# arm_v3.net
KiCad netlist of a schematic drawn in Altium Designer
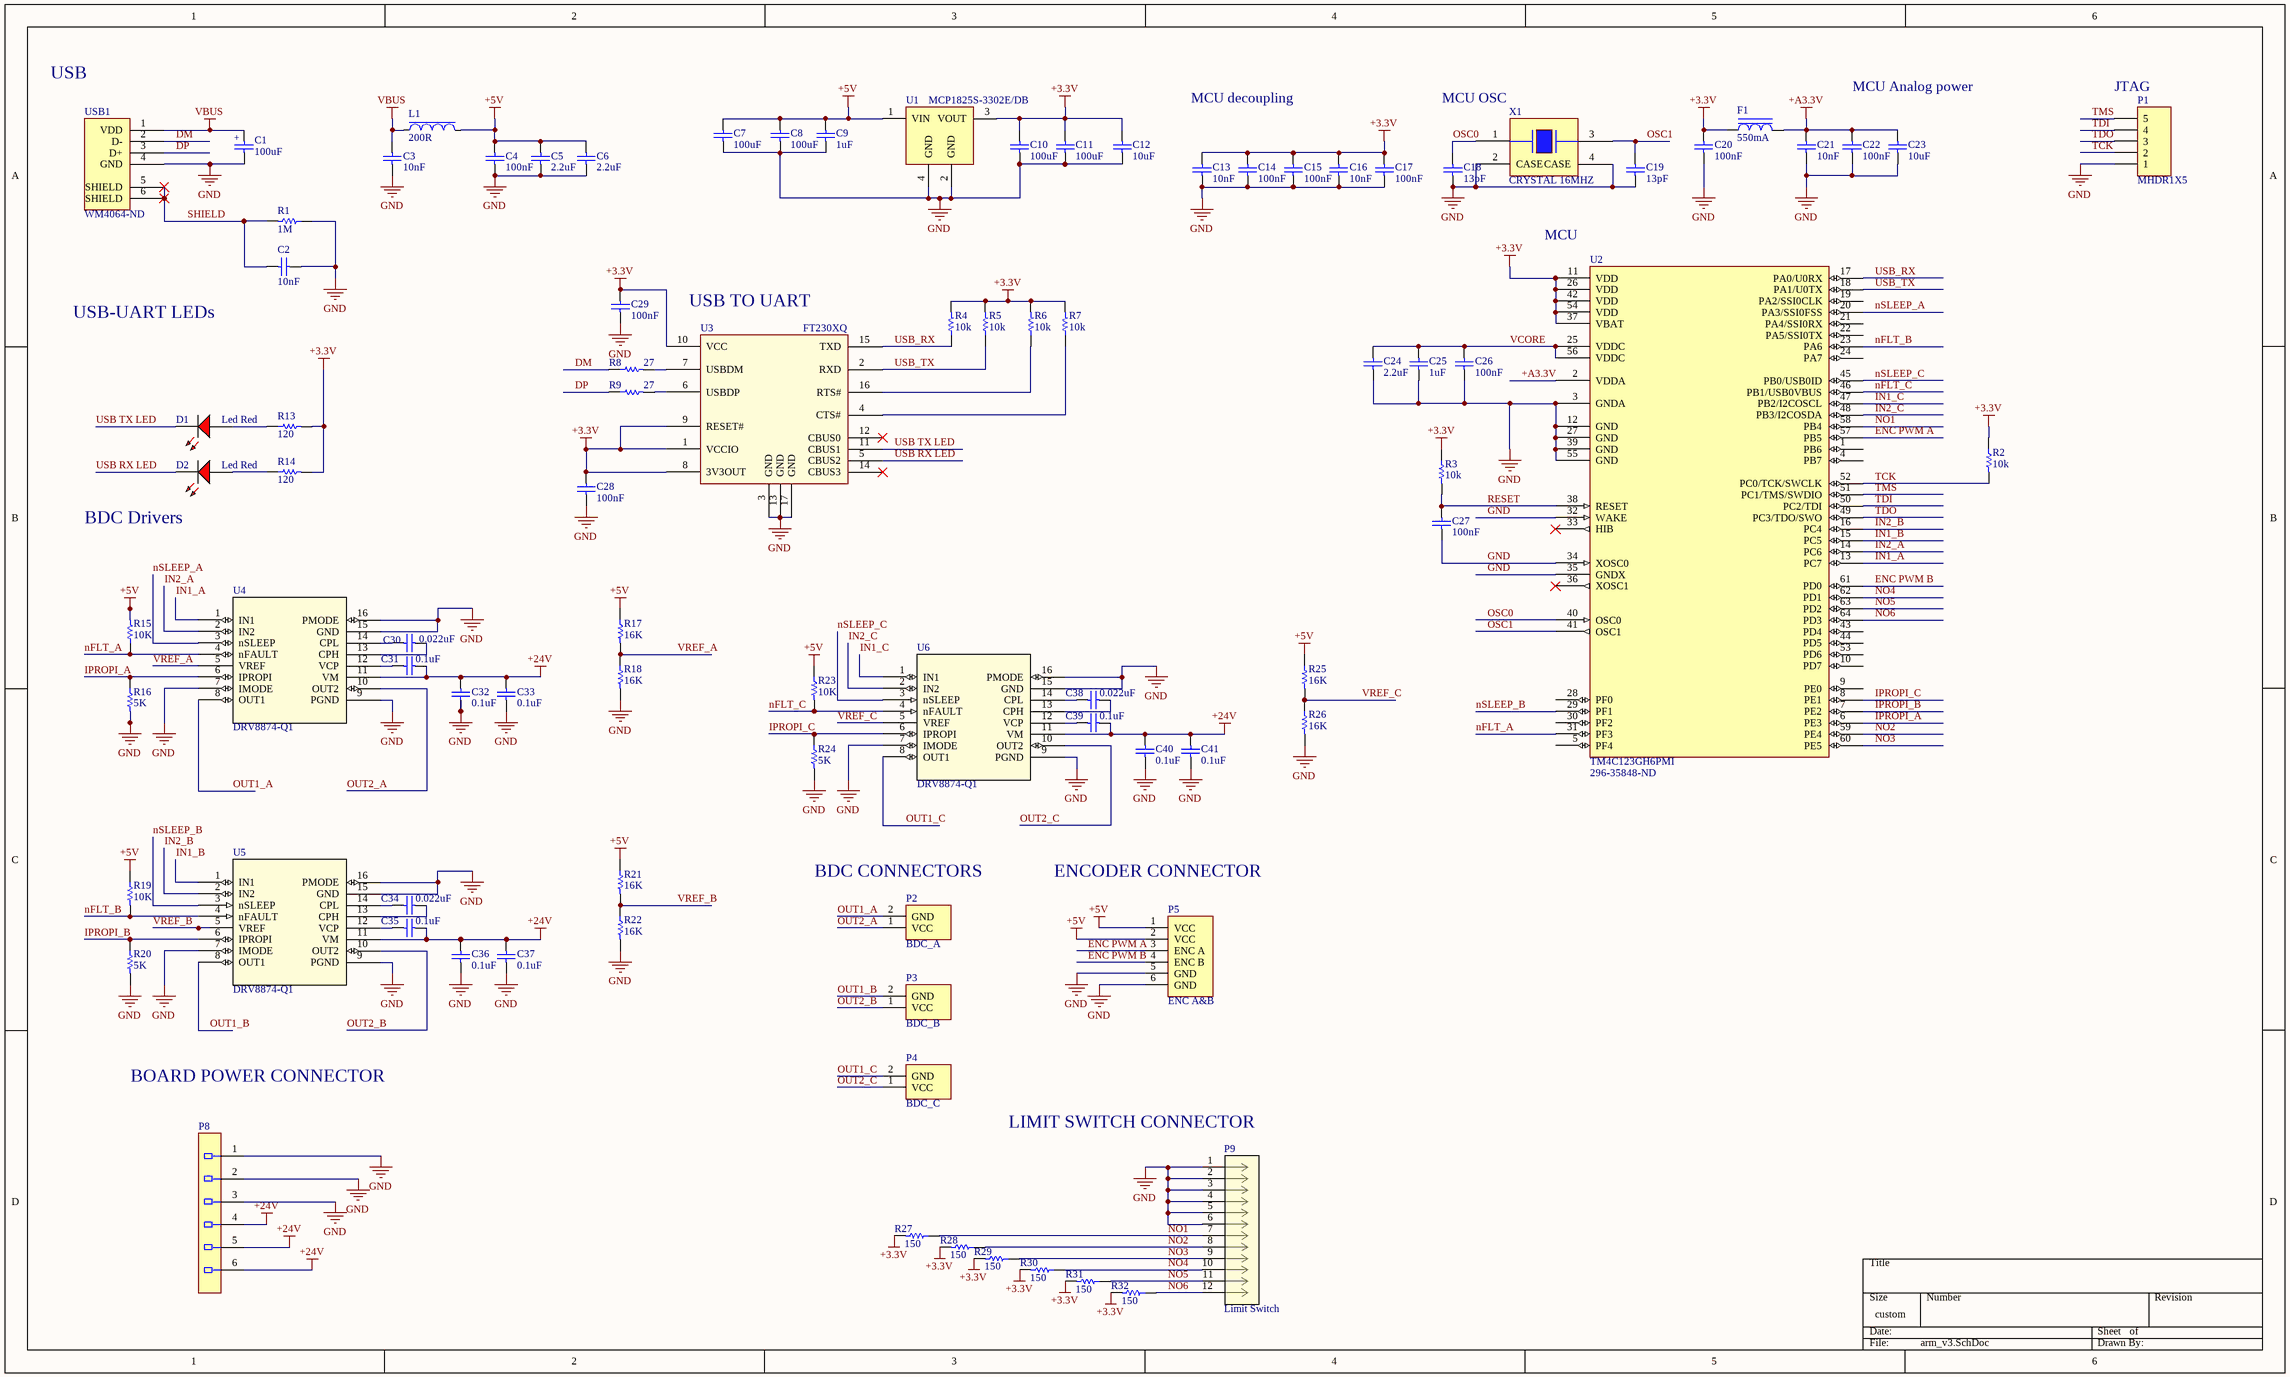
[diagram p0: arm_v3.SchDoc]

(export (version "E")
  (design (tool "Eeschema 10.0.6"))
  (components
    (comp (ref "C1")
      (value "100uF")
      (footprint "CapAlu6.3mmx12.5mm")
      (description "Capacitor 35v 100uF 6.3mm")
      (fields
        (field (name "MANUFACTURER") "Nichicon")
        (field (name "MANUFACTURER PART NUMBER") "UHV1V101MED")
      )
      (libsource (lib "Capacitors") (part "100uF_35v_6.3x12.5"))
    )
    (comp (ref "C2")
      (value "10nF")
      (footprint "CAP_1206")
      (description "CAP CER 10000PF 500V X7R 1206")
      (fields
        (field (name "MANUFACTURER") "Samsung Electro-Mechanics America, Inc")
        (field (name "MANUFACTURER PART NUMBER") "CL31B103KGFNNNE")
      )
      (libsource (lib "Capacitors") (part "10nF_500V_1206"))
    )
    (comp (ref "C3")
      (value "10nF")
      (footprint "CAP_0402_M")
      (description "CAP CER 10000PF 50V 10% X7R 0402")
      (fields
        (field (name "MANUFACTURER") "Kemet")
        (field (name "MANUFACTURER PART NUMBER") "C0402C103K5RACTU")
      )
      (libsource (lib "Capacitors") (part "10nF_50V_0402"))
    )
    (comp (ref "C4")
      (value "100nF")
      (footprint "CAP_0402_M")
      (description "CAP CER 100NF 50V 20% X5R 0402")
      (fields
        (field (name "MANUFACTURER") "TDK Corporation")
        (field (name "MANUFACTURER PART NUMBER") "C1005X5R1H104M050BB")
      )
      (libsource (lib "Capacitors") (part "100nF_50V_0402"))
    )
    (comp (ref "C5")
      (value "2.2uF")
      (footprint "CAP_0402_M")
      (description "CAP CER 2.2UF 10V 20% X5R 0402")
      (fields
        (field (name "MANUFACTURER") "Taiyo Yuden")
        (field (name "MANUFACTURER PART NUMBER") "LMK105BJ225MV-F")
      )
      (libsource (lib "Capacitors") (part "2.2uF_10V_0402"))
    )
    (comp (ref "C6")
      (value "2.2uF")
      (footprint "CAP_0402_M")
      (description "CAP CER 2.2UF 10V 20% X5R 0402")
      (fields
        (field (name "MANUFACTURER") "Taiyo Yuden")
        (field (name "MANUFACTURER PART NUMBER") "LMK105BJ225MV-F")
      )
      (libsource (lib "Capacitors") (part "2.2uF_10V_0402"))
    )
    (comp (ref "C7")
      (value "100uF")
      (footprint "CAP_1206")
      (description "CAP CER 100UF 6.3V X5R 1206")
      (fields
        (field (name "MANUFACTURER") "Murata Electronics North America")
        (field (name "MANUFACTURER PART NUMBER") "GRM31CR60J107ME39L")
      )
      (libsource (lib "Capacitors") (part "100uF_6.3v_1206_X5R"))
    )
    (comp (ref "C8")
      (value "100uF")
      (footprint "CAP_1206")
      (description "CAP CER 100UF 6.3V X5R 1206")
      (fields
        (field (name "MANUFACTURER") "Murata Electronics North America")
        (field (name "MANUFACTURER PART NUMBER") "GRM31CR60J107ME39L")
      )
      (libsource (lib "Capacitors") (part "100uF_6.3v_1206_X5R"))
    )
    (comp (ref "C9")
      (value "1uF")
      (footprint "CAP_0402_M")
      (description "CAP CER 1UF 25V 10% X5R 0402")
      (fields
        (field (name "MANUFACTURER") "TDK Corporation")
        (field (name "MANUFACTURER PART NUMBER") "C1005X5R1E105K050BC")
      )
      (libsource (lib "Capacitors") (part "1uF_25V_0402"))
    )
    (comp (ref "C10")
      (value "100uF")
      (footprint "CAP_1206")
      (description "CAP CER 100UF 6.3V X5R 1206")
      (fields
        (field (name "MANUFACTURER") "Murata Electronics North America")
        (field (name "MANUFACTURER PART NUMBER") "GRM31CR60J107ME39L")
      )
      (libsource (lib "Capacitors") (part "100uF_6.3v_1206_X5R"))
    )
    (comp (ref "C11")
      (value "100uF")
      (footprint "CAP_1206")
      (description "CAP CER 100UF 6.3V X5R 1206")
      (fields
        (field (name "MANUFACTURER") "Murata Electronics North America")
        (field (name "MANUFACTURER PART NUMBER") "GRM31CR60J107ME39L")
      )
      (libsource (lib "Capacitors") (part "100uF_6.3v_1206_X5R"))
    )
    (comp (ref "C12")
      (value "10uF")
      (footprint "CAP_0603")
      (description "CAP CER 10UF 10V 20% X5R 0603")
      (fields
        (field (name "MANUFACTURER") "Taiyo Yuden")
        (field (name "MANUFACTURER PART NUMBER") "LMK107BBJ106MAHT")
      )
      (libsource (lib "Capacitors") (part "10uF_10V_0603"))
    )
    (comp (ref "C13")
      (value "10nF")
      (footprint "CAP_0402_M")
      (description "CAP CER 10000PF 50V 10% X7R 0402")
      (fields
        (field (name "MANUFACTURER") "Kemet")
        (field (name "MANUFACTURER PART NUMBER") "C0402C103K5RACTU")
      )
      (libsource (lib "Capacitors") (part "10nF_50V_0402"))
    )
    (comp (ref "C14")
      (value "100nF")
      (footprint "CAP_0402_M")
      (description "CAP CER 100NF 50V 20% X5R 0402")
      (fields
        (field (name "MANUFACTURER") "TDK Corporation")
        (field (name "MANUFACTURER PART NUMBER") "C1005X5R1H104M050BB")
      )
      (libsource (lib "Capacitors") (part "100nF_50V_0402"))
    )
    (comp (ref "C15")
      (value "100nF")
      (footprint "CAP_0402_M")
      (description "CAP CER 100NF 50V 20% X5R 0402")
      (fields
        (field (name "MANUFACTURER") "TDK Corporation")
        (field (name "MANUFACTURER PART NUMBER") "C1005X5R1H104M050BB")
      )
      (libsource (lib "Capacitors") (part "100nF_50V_0402"))
    )
    (comp (ref "C16")
      (value "10nF")
      (footprint "CAP_0402_M")
      (description "CAP CER 10000PF 50V 10% X7R 0402")
      (fields
        (field (name "MANUFACTURER") "Kemet")
        (field (name "MANUFACTURER PART NUMBER") "C0402C103K5RACTU")
      )
      (libsource (lib "Capacitors") (part "10nF_50V_0402"))
    )
    (comp (ref "C17")
      (value "100nF")
      (footprint "CAP_0402_M")
      (description "CAP CER 100NF 50V 20% X5R 0402")
      (fields
        (field (name "MANUFACTURER") "TDK Corporation")
        (field (name "MANUFACTURER PART NUMBER") "C1005X5R1H104M050BB")
      )
      (libsource (lib "Capacitors") (part "100nF_50V_0402"))
    )
    (comp (ref "C18")
      (value "13pF")
      (footprint "CAP_0402_M")
      (description "CAP CER 13PF 50V 5% NP0 0402")
      (fields
        (field (name "MANUFACTURER") "Samsung Electro-Mechanics America, Inc")
        (field (name "MANUFACTURER PART NUMBER") "CL05C130JB5NNNC")
      )
      (libsource (lib "Capacitors") (part "13pF_50V_0402"))
    )
    (comp (ref "C19")
      (value "13pF")
      (footprint "CAP_0402_M")
      (description "CAP CER 13PF 50V 5% NP0 0402")
      (fields
        (field (name "MANUFACTURER") "Samsung Electro-Mechanics America, Inc")
        (field (name "MANUFACTURER PART NUMBER") "CL05C130JB5NNNC")
      )
      (libsource (lib "Capacitors") (part "13pF_50V_0402"))
    )
    (comp (ref "C20")
      (value "100nF")
      (footprint "CAP_0402_M")
      (description "CAP CER 100NF 50V 20% X5R 0402")
      (fields
        (field (name "MANUFACTURER") "TDK Corporation")
        (field (name "MANUFACTURER PART NUMBER") "C1005X5R1H104M050BB")
      )
      (libsource (lib "Capacitors") (part "100nF_50V_0402"))
    )
    (comp (ref "C21")
      (value "10nF")
      (footprint "CAP_0402_M")
      (description "CAP CER 10000PF 50V 10% X7R 0402")
      (fields
        (field (name "MANUFACTURER") "Kemet")
        (field (name "MANUFACTURER PART NUMBER") "C0402C103K5RACTU")
      )
      (libsource (lib "Capacitors") (part "10nF_50V_0402"))
    )
    (comp (ref "C22")
      (value "100nF")
      (footprint "CAP_0402_M")
      (description "CAP CER 100NF 50V 20% X5R 0402")
      (fields
        (field (name "MANUFACTURER") "TDK Corporation")
        (field (name "MANUFACTURER PART NUMBER") "C1005X5R1H104M050BB")
      )
      (libsource (lib "Capacitors") (part "100nF_50V_0402"))
    )
    (comp (ref "C23")
      (value "10uF")
      (footprint "CAP_0603")
      (description "CAP CER 10UF 10V 20% X5R 0603")
      (fields
        (field (name "MANUFACTURER") "Taiyo Yuden")
        (field (name "MANUFACTURER PART NUMBER") "LMK107BBJ106MAHT")
      )
      (libsource (lib "Capacitors") (part "10uF_10V_0603"))
    )
    (comp (ref "C24")
      (value "2.2uF")
      (footprint "CAP_0603")
      (description "CAP CER 2.2UF 35V 10% X5R 0603")
      (fields
        (field (name "MANUFACTURER") "Murata Electronics North America")
        (field (name "MANUFACTURER PART NUMBER") "GRM188R6YA225KA12D")
      )
      (libsource (lib "Capacitors") (part "2.2uF_35V_0603"))
    )
    (comp (ref "C25")
      (value "1uF")
      (footprint "CAP_0402_M")
      (description "CAP CER 1UF 25V 10% X5R 0402")
      (fields
        (field (name "MANUFACTURER") "TDK Corporation")
        (field (name "MANUFACTURER PART NUMBER") "C1005X5R1E105K050BC")
      )
      (libsource (lib "Capacitors") (part "1uF_25V_0402"))
    )
    (comp (ref "C26")
      (value "100nF")
      (footprint "CAP_0402_M")
      (description "CAP CER 100NF 50V 20% X5R 0402")
      (fields
        (field (name "MANUFACTURER") "TDK Corporation")
        (field (name "MANUFACTURER PART NUMBER") "C1005X5R1H104M050BB")
      )
      (libsource (lib "Capacitors") (part "100nF_50V_0402"))
    )
    (comp (ref "C27")
      (value "100nF")
      (footprint "CAP_0402_M")
      (description "CAP CER 100NF 50V 20% X5R 0402")
      (fields
        (field (name "MANUFACTURER") "TDK Corporation")
        (field (name "MANUFACTURER PART NUMBER") "C1005X5R1H104M050BB")
      )
      (libsource (lib "Capacitors") (part "100nF_50V_0402"))
    )
    (comp (ref "C28")
      (value "100nF")
      (footprint "CAP_0402_M")
      (description "CAP CER 100NF 50V 20% X5R 0402")
      (fields
        (field (name "MANUFACTURER") "TDK Corporation")
        (field (name "MANUFACTURER PART NUMBER") "C1005X5R1H104M050BB")
      )
      (libsource (lib "Capacitors") (part "100nF_50V_0402"))
    )
    (comp (ref "C29")
      (value "100nF")
      (footprint "CAP_0402_M")
      (description "CAP CER 100NF 50V 20% X5R 0402")
      (fields
        (field (name "MANUFACTURER") "TDK Corporation")
        (field (name "MANUFACTURER PART NUMBER") "C1005X5R1H104M050BB")
      )
      (libsource (lib "Capacitors") (part "100nF_50V_0402"))
    )
    (comp (ref "C30")
      (value "0.022uF")
      (footprint "CAP_0402_M")
      (description "CAP CER 100NF 50V 20% X5R 0402")
      (fields
        (field (name "MANUFACTURER") "TDK Corporation")
        (field (name "MANUFACTURER PART NUMBER") "C1005X5R1H104M050BB")
      )
      (libsource (lib "Capacitors") (part "100nF_50V_0402"))
    )
    (comp (ref "C31")
      (value "0.1uF")
      (footprint "CAP_0402_M")
      (description "CAP CER 100NF 50V 20% X5R 0402")
      (fields
        (field (name "MANUFACTURER") "TDK Corporation")
        (field (name "MANUFACTURER PART NUMBER") "C1005X5R1H104M050BB")
      )
      (libsource (lib "Capacitors") (part "100nF_50V_0402"))
    )
    (comp (ref "C32")
      (value "0.1uF")
      (footprint "CAP_0402_M")
      (description "CAP CER 100NF 50V 20% X5R 0402")
      (fields
        (field (name "MANUFACTURER") "TDK Corporation")
        (field (name "MANUFACTURER PART NUMBER") "C1005X5R1H104M050BB")
      )
      (libsource (lib "Capacitors") (part "100nF_50V_0402"))
    )
    (comp (ref "C33")
      (value "0.1uF")
      (footprint "CAP_0402_M")
      (description "CAP CER 100NF 50V 20% X5R 0402")
      (fields
        (field (name "MANUFACTURER") "TDK Corporation")
        (field (name "MANUFACTURER PART NUMBER") "C1005X5R1H104M050BB")
      )
      (libsource (lib "Capacitors") (part "100nF_50V_0402"))
    )
    (comp (ref "C34")
      (value "0.022uF")
      (footprint "CAP_0402_M")
      (description "CAP CER 100NF 50V 20% X5R 0402")
      (fields
        (field (name "MANUFACTURER") "TDK Corporation")
        (field (name "MANUFACTURER PART NUMBER") "C1005X5R1H104M050BB")
      )
      (libsource (lib "Capacitors") (part "100nF_50V_0402"))
    )
    (comp (ref "C35")
      (value "0.1uF")
      (footprint "CAP_0402_M")
      (description "CAP CER 100NF 50V 20% X5R 0402")
      (fields
        (field (name "MANUFACTURER") "TDK Corporation")
        (field (name "MANUFACTURER PART NUMBER") "C1005X5R1H104M050BB")
      )
      (libsource (lib "Capacitors") (part "100nF_50V_0402"))
    )
    (comp (ref "C36")
      (value "0.1uF")
      (footprint "CAP_0402_M")
      (description "CAP CER 100NF 50V 20% X5R 0402")
      (fields
        (field (name "MANUFACTURER") "TDK Corporation")
        (field (name "MANUFACTURER PART NUMBER") "C1005X5R1H104M050BB")
      )
      (libsource (lib "Capacitors") (part "100nF_50V_0402"))
    )
    (comp (ref "C37")
      (value "0.1uF")
      (footprint "CAP_0402_M")
      (description "CAP CER 100NF 50V 20% X5R 0402")
      (fields
        (field (name "MANUFACTURER") "TDK Corporation")
        (field (name "MANUFACTURER PART NUMBER") "C1005X5R1H104M050BB")
      )
      (libsource (lib "Capacitors") (part "100nF_50V_0402"))
    )
    (comp (ref "C38")
      (value "0.022uF")
      (footprint "CAP_0402_M")
      (description "CAP CER 100NF 50V 20% X5R 0402")
      (fields
        (field (name "MANUFACTURER") "TDK Corporation")
        (field (name "MANUFACTURER PART NUMBER") "C1005X5R1H104M050BB")
      )
      (libsource (lib "Capacitors") (part "100nF_50V_0402"))
    )
    (comp (ref "C39")
      (value "0.1uF")
      (footprint "CAP_0402_M")
      (description "CAP CER 100NF 50V 20% X5R 0402")
      (fields
        (field (name "MANUFACTURER") "TDK Corporation")
        (field (name "MANUFACTURER PART NUMBER") "C1005X5R1H104M050BB")
      )
      (libsource (lib "Capacitors") (part "100nF_50V_0402"))
    )
    (comp (ref "C40")
      (value "0.1uF")
      (footprint "CAP_0402_M")
      (description "CAP CER 100NF 50V 20% X5R 0402")
      (fields
        (field (name "MANUFACTURER") "TDK Corporation")
        (field (name "MANUFACTURER PART NUMBER") "C1005X5R1H104M050BB")
      )
      (libsource (lib "Capacitors") (part "100nF_50V_0402"))
    )
    (comp (ref "C41")
      (value "0.1uF")
      (footprint "CAP_0402_M")
      (description "CAP CER 100NF 50V 20% X5R 0402")
      (fields
        (field (name "MANUFACTURER") "TDK Corporation")
        (field (name "MANUFACTURER PART NUMBER") "C1005X5R1H104M050BB")
      )
      (libsource (lib "Capacitors") (part "100nF_50V_0402"))
    )
    (comp (ref "D1")
      (value "Led Red")
      (footprint "TOPLED 0805")
      (description "LED TOPLED 630NM SUP RED CLR SMD")
      (fields
        (field (name "MANUFACTURER") "OSRAM Opto Semiconductors Inc")
        (field (name "MANUFACTURER PART NUMBER") "LS M67K-H2L1-1-Z")
      )
      (libsource (lib "Diodes") (part "TOPLED 0803"))
    )
    (comp (ref "D2")
      (value "Led Red")
      (footprint "TOPLED 0805")
      (description "LED TOPLED 630NM SUP RED CLR SMD")
      (fields
        (field (name "MANUFACTURER") "OSRAM Opto Semiconductors Inc")
        (field (name "MANUFACTURER PART NUMBER") "LS M67K-H2L1-1-Z")
      )
      (libsource (lib "Diodes") (part "TOPLED 0803"))
    )
    (comp (ref "F1")
      (value "550mA")
      (footprint "RES_0402_M")
      (description "FERRITE CHIP 40 OHM 550MA 0402")
      (fields
        (field (name "MANUFACTURER") "TDK Corporation")
        (field (name "MANUFACTURER PART NUMBER") "MMZ1005Y400CT000")
      )
      (libsource (lib "Resistors") (part "40O_550mA_0402"))
    )
    (comp (ref "L1")
      (value "200R")
      (footprint "IND_0603")
      (description "FILTER CHIP 220 OHM 2A 0603")
      (fields
        (field (name "MANUFACTURER") "Murata Electronics North America")
        (field (name "MANUFACTURER PART NUMBER") "BLM18EG221SN1D")
      )
      (libsource (lib "Inductors") (part "Ferrite_200 ohms_2A"))
    )
    (comp (ref "P1")
      (value "MHDR1X5")
      (footprint "MHDR1X5")
      (description "Header, 5-Pin")
      (fields (field (name "PUBLISHER") "Altium Limited"))
      (libsource (lib "Miscellaneous Connectors") (part "MHDR1X5"))
    )
    (comp (ref "P2")
      (value "BDC_A")
      (footprint "SamacSys:436500227")
      (description "Connector")
      (fields (field (name "MANUFACTURER_PART_NUMBER") "43650-0227"))
      (libsource (lib "*") (part "43650-0227"))
    )
    (comp (ref "P3")
      (value "BDC_B")
      (footprint "SamacSys:436500227")
      (description "Connector")
      (fields (field (name "MANUFACTURER_PART_NUMBER") "43650-0227"))
      (libsource (lib "*") (part "43650-0227"))
    )
    (comp (ref "P4")
      (value "BDC_C")
      (footprint "SamacSys:436500227")
      (description "Connector")
      (fields (field (name "MANUFACTURER_PART_NUMBER") "43650-0227"))
      (libsource (lib "*") (part "43650-0227"))
    )
    (comp (ref "P5")
      (value "ENC A&B")
      (footprint "SamacSys:1053091106")
      (description "Connector")
      (fields (field (name "MANUFACTURER_PART_NUMBER") "105309-1106"))
      (libsource (lib "*") (part "105309-1106"))
    )
    (comp (ref "P8") (value "76825-0006") (libsource (lib "Molex 76825-0006") (part "76825-0006")))
    (comp (ref "P9")
      (value "Limit Switch")
      (footprint "CON_1053141112")
      (description "No Description Available")
      (fields
        (field (name "MANUFACTURER_PART_NUMBER") "1053141112")
        (field (name "COPYRIGHT") "Copyright (C) 2018 Accelerated Designs. All rights reserved")
      )
      (libsource (lib "Molex 1053141112") (part "1053141112"))
    )
    (comp (ref "R1")
      (value "1M")
      (footprint "RES_1206")
      (description "RES SMD 1M OHM 5% 1/4W 1206")
      (fields
        (field (name "MANUFACTURER") "Panasonic Electronic Components")
        (field (name "MANUFACTURER PART NUMBER") "ERJ-8GEYJ105V")
      )
      (libsource (lib "Resistors") (part "1M_5%_1206"))
    )
    (comp (ref "R2")
      (value "10k")
      (footprint "RES_0402_M")
      (description "RES SMD 10K OHM 1% 1/10W 0402")
      (fields
        (field (name "MANUFACTURER") "Panasonic Electronic Components")
        (field (name "MANUFACTURER PART NUMBER") "ERJ-2RKF1002X")
      )
      (libsource (lib "Resistors") (part "10k_1%_0402"))
    )
    (comp (ref "R3")
      (value "10k")
      (footprint "RES_0402_M")
      (description "RES SMD 10K OHM 1% 1/10W 0402")
      (fields
        (field (name "MANUFACTURER") "Panasonic Electronic Components")
        (field (name "MANUFACTURER PART NUMBER") "ERJ-2RKF1002X")
      )
      (libsource (lib "Resistors") (part "10k_1%_0402"))
    )
    (comp (ref "R4")
      (value "10k")
      (footprint "RES_0402_M")
      (description "RES SMD 10K OHM 1% 1/10W 0402")
      (fields
        (field (name "MANUFACTURER") "Panasonic Electronic Components")
        (field (name "MANUFACTURER PART NUMBER") "ERJ-2RKF1002X")
      )
      (libsource (lib "Resistors") (part "10k_1%_0402"))
    )
    (comp (ref "R5")
      (value "10k")
      (footprint "RES_0402_M")
      (description "RES SMD 10K OHM 1% 1/10W 0402")
      (fields
        (field (name "MANUFACTURER") "Panasonic Electronic Components")
        (field (name "MANUFACTURER PART NUMBER") "ERJ-2RKF1002X")
      )
      (libsource (lib "Resistors") (part "10k_1%_0402"))
    )
    (comp (ref "R6")
      (value "10k")
      (footprint "RES_0402_M")
      (description "RES SMD 10K OHM 1% 1/10W 0402")
      (fields
        (field (name "MANUFACTURER") "Panasonic Electronic Components")
        (field (name "MANUFACTURER PART NUMBER") "ERJ-2RKF1002X")
      )
      (libsource (lib "Resistors") (part "10k_1%_0402"))
    )
    (comp (ref "R7")
      (value "10k")
      (footprint "RES_0402_M")
      (description "RES SMD 10K OHM 1% 1/10W 0402")
      (fields
        (field (name "MANUFACTURER") "Panasonic Electronic Components")
        (field (name "MANUFACTURER PART NUMBER") "ERJ-2RKF1002X")
      )
      (libsource (lib "Resistors") (part "10k_1%_0402"))
    )
    (comp (ref "R8")
      (value "27")
      (footprint "RES_0402_M")
      (description "RES SMD 27 OHM 1% 1/10W 0402")
      (fields
        (field (name "MANUFACTURER") "Panasonic Electronic Components")
        (field (name "MANUFACTURER PART NUMBER") "ERJ-2RKF27R0X")
      )
      (libsource (lib "Resistors") (part "27_1%_0402"))
    )
    (comp (ref "R9")
      (value "27")
      (footprint "RES_0402_M")
      (description "RES SMD 27 OHM 1% 1/10W 0402")
      (fields
        (field (name "MANUFACTURER") "Panasonic Electronic Components")
        (field (name "MANUFACTURER PART NUMBER") "ERJ-2RKF27R0X")
      )
      (libsource (lib "Resistors") (part "27_1%_0402"))
    )
    (comp (ref "R13")
      (value "120")
      (footprint "RES_0402_M")
      (description "RES SMD 120 OHM 1% 1/10W 0402")
      (fields
        (field (name "MANUFACTURER") "Panasonic Electronic Components")
        (field (name "MANUFACTURER PART NUMBER") "ERJ-2RKF1200X")
      )
      (libsource (lib "Resistors") (part "120_1%_0402"))
    )
    (comp (ref "R14")
      (value "120")
      (footprint "RES_0402_M")
      (description "RES SMD 120 OHM 1% 1/10W 0402")
      (fields
        (field (name "MANUFACTURER") "Panasonic Electronic Components")
        (field (name "MANUFACTURER PART NUMBER") "ERJ-2RKF1200X")
      )
      (libsource (lib "Resistors") (part "120_1%_0402"))
    )
    (comp (ref "R15")
      (value "10K")
      (footprint "RES_0402_M")
      (description "RES SMD 0 OHM JUMPER 1/16W 0402")
      (fields
        (field (name "MANUFACTURER") "Yageo")
        (field (name "MANUFACTURER PART NUMBER") "RC0402FR-070RL")
      )
      (libsource (lib "Resistors") (part "0_0402"))
    )
    (comp (ref "R16")
      (value "5K")
      (footprint "RES_0402_M")
      (description "RES SMD 0 OHM JUMPER 1/16W 0402")
      (fields
        (field (name "MANUFACTURER") "Yageo")
        (field (name "MANUFACTURER PART NUMBER") "RC0402FR-070RL")
      )
      (libsource (lib "Resistors") (part "0_0402"))
    )
    (comp (ref "R17")
      (value "16K")
      (footprint "RES_0402_M")
      (description "RES SMD 0 OHM JUMPER 1/16W 0402")
      (fields
        (field (name "MANUFACTURER") "Yageo")
        (field (name "MANUFACTURER PART NUMBER") "RC0402FR-070RL")
      )
      (libsource (lib "Resistors") (part "0_0402"))
    )
    (comp (ref "R18")
      (value "16K")
      (footprint "RES_0402_M")
      (description "RES SMD 0 OHM JUMPER 1/16W 0402")
      (fields
        (field (name "MANUFACTURER") "Yageo")
        (field (name "MANUFACTURER PART NUMBER") "RC0402FR-070RL")
      )
      (libsource (lib "Resistors") (part "0_0402"))
    )
    (comp (ref "R19")
      (value "10K")
      (footprint "RES_0402_M")
      (description "RES SMD 0 OHM JUMPER 1/16W 0402")
      (fields
        (field (name "MANUFACTURER") "Yageo")
        (field (name "MANUFACTURER PART NUMBER") "RC0402FR-070RL")
      )
      (libsource (lib "Resistors") (part "0_0402"))
    )
    (comp (ref "R20")
      (value "5K")
      (footprint "RES_0402_M")
      (description "RES SMD 0 OHM JUMPER 1/16W 0402")
      (fields
        (field (name "MANUFACTURER") "Yageo")
        (field (name "MANUFACTURER PART NUMBER") "RC0402FR-070RL")
      )
      (libsource (lib "Resistors") (part "0_0402"))
    )
    (comp (ref "R21")
      (value "16K")
      (footprint "RES_0402_M")
      (description "RES SMD 0 OHM JUMPER 1/16W 0402")
      (fields
        (field (name "MANUFACTURER") "Yageo")
        (field (name "MANUFACTURER PART NUMBER") "RC0402FR-070RL")
      )
      (libsource (lib "Resistors") (part "0_0402"))
    )
    (comp (ref "R22")
      (value "16K")
      (footprint "RES_0402_M")
      (description "RES SMD 0 OHM JUMPER 1/16W 0402")
      (fields
        (field (name "MANUFACTURER") "Yageo")
        (field (name "MANUFACTURER PART NUMBER") "RC0402FR-070RL")
      )
      (libsource (lib "Resistors") (part "0_0402"))
    )
    (comp (ref "R23")
      (value "10K")
      (footprint "RES_0402_M")
      (description "RES SMD 0 OHM JUMPER 1/16W 0402")
      (fields
        (field (name "MANUFACTURER") "Yageo")
        (field (name "MANUFACTURER PART NUMBER") "RC0402FR-070RL")
      )
      (libsource (lib "Resistors") (part "0_0402"))
    )
    (comp (ref "R24")
      (value "5K")
      (footprint "RES_0402_M")
      (description "RES SMD 0 OHM JUMPER 1/16W 0402")
      (fields
        (field (name "MANUFACTURER") "Yageo")
        (field (name "MANUFACTURER PART NUMBER") "RC0402FR-070RL")
      )
      (libsource (lib "Resistors") (part "0_0402"))
    )
    (comp (ref "R25")
      (value "16K")
      (footprint "RES_0402_M")
      (description "RES SMD 0 OHM JUMPER 1/16W 0402")
      (fields
        (field (name "MANUFACTURER") "Yageo")
        (field (name "MANUFACTURER PART NUMBER") "RC0402FR-070RL")
      )
      (libsource (lib "Resistors") (part "0_0402"))
    )
    (comp (ref "R26")
      (value "16K")
      (footprint "RES_0402_M")
      (description "RES SMD 0 OHM JUMPER 1/16W 0402")
      (fields
        (field (name "MANUFACTURER") "Yageo")
        (field (name "MANUFACTURER PART NUMBER") "RC0402FR-070RL")
      )
      (libsource (lib "Resistors") (part "0_0402"))
    )
    (comp (ref "R27")
      (value "150")
      (footprint "RES_0402_M")
      (description "RES SMD 10K OHM 1% 1/10W 0402")
      (fields
        (field (name "MANUFACTURER") "Panasonic Electronic Components")
        (field (name "MANUFACTURER PART NUMBER") "ERJ-2RKF1002X")
      )
      (libsource (lib "Resistors") (part "10k_1%_0402"))
    )
    (comp (ref "R28")
      (value "150")
      (footprint "RES_0402_M")
      (description "RES SMD 10K OHM 1% 1/10W 0402")
      (fields
        (field (name "MANUFACTURER") "Panasonic Electronic Components")
        (field (name "MANUFACTURER PART NUMBER") "ERJ-2RKF1002X")
      )
      (libsource (lib "Resistors") (part "10k_1%_0402"))
    )
    (comp (ref "R29")
      (value "150")
      (footprint "RES_0402_M")
      (description "RES SMD 10K OHM 1% 1/10W 0402")
      (fields
        (field (name "MANUFACTURER") "Panasonic Electronic Components")
        (field (name "MANUFACTURER PART NUMBER") "ERJ-2RKF1002X")
      )
      (libsource (lib "Resistors") (part "10k_1%_0402"))
    )
    (comp (ref "R30")
      (value "150")
      (footprint "RES_0402_M")
      (description "RES SMD 10K OHM 1% 1/10W 0402")
      (fields
        (field (name "MANUFACTURER") "Panasonic Electronic Components")
        (field (name "MANUFACTURER PART NUMBER") "ERJ-2RKF1002X")
      )
      (libsource (lib "Resistors") (part "10k_1%_0402"))
    )
    (comp (ref "R31")
      (value "150")
      (footprint "RES_0402_M")
      (description "RES SMD 10K OHM 1% 1/10W 0402")
      (fields
        (field (name "MANUFACTURER") "Panasonic Electronic Components")
        (field (name "MANUFACTURER PART NUMBER") "ERJ-2RKF1002X")
      )
      (libsource (lib "Resistors") (part "10k_1%_0402"))
    )
    (comp (ref "R32")
      (value "150")
      (footprint "RES_0402_M")
      (description "RES SMD 10K OHM 1% 1/10W 0402")
      (fields
        (field (name "MANUFACTURER") "Panasonic Electronic Components")
        (field (name "MANUFACTURER PART NUMBER") "ERJ-2RKF1002X")
      )
      (libsource (lib "Resistors") (part "10k_1%_0402"))
    )
    (comp (ref "U1")
      (value "MCP1825S-3302E/DB")
      (footprint "SOT230P700X180-4N")
      (description "500 mA, Low Voltage, Low Quiescent Current LDO Regulator")
      (fields (field (name "MANUFACTURER") "Microchip Technology"))
      (libsource (lib "ICs") (part "MCP1825S-3302E/DB"))
    )
    (comp (ref "U2")
      (value "TM4C123GH6PMI")
      (footprint "TSQFP50P1200X1200X120-64N")
      (description "Tiva TM4C123GH6PM Microcontroller ARM Cortex 80 MHz FPU")
      (fields (field (name "SUPPLIER PART NUMBER 1") "296-35848-ND"))
      (libsource (lib "ICs") (part "TM4C123GH6PMI"))
    )
    (comp (ref "U3")
      (value "FT230XQ")
      (footprint "QFN65P400X400X80_HS-17N")
      (description "IC USB SERIAL BASIC UART 16QFN")
      (fields
        (field (name "MANUFACTURER") "FTDI, Future Technology Devices International Ltd")
        (field (name "MANUFACTURER PART NUMBER") "FT230XQ-R")
      )
      (libsource (lib "ICs") (part "FT230XQ-R"))
    )
    (comp (ref "U4")
      (value "DRV8874-Q1")
      (footprint "SOIC_PWPRQ1_TEX")
      (description "No Description Available")
      (fields
        (field (name "MANUFACTURER_PART_NUMBER") "DRV8876QPWPRQ1")
        (field (name "COPYRIGHT") "Copyright (C) 2018 Accelerated Designs. All rights reserved")
      )
      (libsource (lib "DRV8876") (part "DRV8876QPWPRQ1"))
    )
    (comp (ref "U5")
      (value "DRV8874-Q1")
      (footprint "SOIC_PWPRQ1_TEX")
      (description "No Description Available")
      (fields
        (field (name "MANUFACTURER_PART_NUMBER") "DRV8876QPWPRQ1")
        (field (name "COPYRIGHT") "Copyright (C) 2018 Accelerated Designs. All rights reserved")
      )
      (libsource (lib "DRV8876") (part "DRV8876QPWPRQ1"))
    )
    (comp (ref "U6")
      (value "DRV8874-Q1")
      (footprint "SOIC_PWPRQ1_TEX")
      (description "No Description Available")
      (fields
        (field (name "MANUFACTURER_PART_NUMBER") "DRV8876QPWPRQ1")
        (field (name "COPYRIGHT") "Copyright (C) 2018 Accelerated Designs. All rights reserved")
      )
      (libsource (lib "DRV8876") (part "DRV8876QPWPRQ1"))
    )
    (comp (ref "USB1")
      (value "USB type-B jack")
      (footprint "USB2.5-2H4E")
      (fields (field (name "SUPPLIER PART NUMBER 1") "WM4064-ND"))
      (libsource (lib "Connectors") (part "MOLEX 0670688010"))
    )
    (comp (ref "X1")
      (value "CRYSTAL 16MHZ")
      (footprint "CRYSTAL_3.2x2.5")
      (description "CRYSTAL 16MHZ 20PF SMD")
      (fields
        (field (name "MANUFACTURER") "CTS-Frequency Controls")
        (field (name "MANUFACTURER PART NUMBER") "403C35E16M00000")
      )
      (libsource (lib "ICs") (part "403C35E16M00000"))
    )
  )
  (nets
    (net (code "1") (name "+3.3V") (class "Default")
      (node (ref "C10") (pin "1") (pinfunction "1_1") (pintype "passive"))
      (node (ref "C11") (pin "1") (pinfunction "1_1") (pintype "passive"))
      (node (ref "C12") (pin "1") (pinfunction "1_1") (pintype "passive"))
      (node (ref "C13") (pin "2") (pinfunction "2_2") (pintype "passive"))
      (node (ref "C14") (pin "2") (pinfunction "2_2") (pintype "passive"))
      (node (ref "C15") (pin "2") (pinfunction "2_2") (pintype "passive"))
      (node (ref "C16") (pin "2") (pinfunction "2_2") (pintype "passive"))
      (node (ref "C17") (pin "2") (pinfunction "2_2") (pintype "passive"))
      (node (ref "C20") (pin "2") (pinfunction "2_2") (pintype "passive"))
      (node (ref "C28") (pin "2") (pinfunction "2_2") (pintype "passive"))
      (node (ref "C29") (pin "2") (pinfunction "2_2") (pintype "passive"))
      (node (ref "F1") (pin "1") (pinfunction "1_1") (pintype "passive"))
      (node (ref "R13") (pin "2") (pinfunction "2_2") (pintype "passive"))
      (node (ref "R14") (pin "2") (pinfunction "2_2") (pintype "passive"))
      (node (ref "R2") (pin "1") (pinfunction "1_1") (pintype "passive"))
      (node (ref "R27") (pin "2") (pinfunction "2_2") (pintype "passive"))
      (node (ref "R28") (pin "2") (pinfunction "2_2") (pintype "passive"))
      (node (ref "R29") (pin "2") (pinfunction "2_2") (pintype "passive"))
      (node (ref "R3") (pin "1") (pinfunction "1_1") (pintype "passive"))
      (node (ref "R30") (pin "2") (pinfunction "2_2") (pintype "passive"))
      (node (ref "R31") (pin "2") (pinfunction "2_2") (pintype "passive"))
      (node (ref "R32") (pin "2") (pinfunction "2_2") (pintype "passive"))
      (node (ref "R4") (pin "2") (pinfunction "2_2") (pintype "passive"))
      (node (ref "R5") (pin "2") (pinfunction "2_2") (pintype "passive"))
      (node (ref "R6") (pin "2") (pinfunction "2_2") (pintype "passive"))
      (node (ref "R7") (pin "2") (pinfunction "2_2") (pintype "passive"))
      (node (ref "U1") (pin "3") (pinfunction "VOUT_3") (pintype "power_in"))
      (node (ref "U2") (pin "11") (pinfunction "VDD_11") (pintype "power_in"))
      (node (ref "U2") (pin "26") (pinfunction "VDD_26") (pintype "power_in"))
      (node (ref "U2") (pin "37") (pinfunction "VBAT_37") (pintype "power_in"))
      (node (ref "U2") (pin "42") (pinfunction "VDD_42") (pintype "power_in"))
      (node (ref "U2") (pin "54") (pinfunction "VDD_54") (pintype "power_in"))
      (node (ref "U3") (pin "1") (pinfunction "VCCIO_1") (pintype "passive"))
      (node (ref "U3") (pin "10") (pinfunction "VCC_10") (pintype "passive"))
      (node (ref "U3") (pin "8") (pinfunction "3V3OUT_8") (pintype "passive"))
      (node (ref "U3") (pin "9") (pinfunction "RESET#_9") (pintype "passive"))
    )
    (net (code "2") (name "+5V") (class "Default")
      (node (ref "C4") (pin "2") (pinfunction "2_2") (pintype "passive"))
      (node (ref "C5") (pin "2") (pinfunction "2_2") (pintype "passive"))
      (node (ref "C6") (pin "2") (pinfunction "2_2") (pintype "passive"))
      (node (ref "C7") (pin "1") (pinfunction "1_1") (pintype "passive"))
      (node (ref "C8") (pin "1") (pinfunction "1_1") (pintype "passive"))
      (node (ref "C9") (pin "2") (pinfunction "2_2") (pintype "passive"))
      (node (ref "L1") (pin "2") (pinfunction "2_2") (pintype "passive"))
      (node (ref "P5") (pin "1") (pinfunction "VCC_1") (pintype "passive"))
      (node (ref "P5") (pin "2") (pinfunction "VCC_2") (pintype "passive"))
      (node (ref "R15") (pin "2") (pinfunction "2_2") (pintype "passive"))
      (node (ref "R17") (pin "1") (pinfunction "1_1") (pintype "passive"))
      (node (ref "R19") (pin "1") (pinfunction "1_1") (pintype "passive"))
      (node (ref "R21") (pin "1") (pinfunction "1_1") (pintype "passive"))
      (node (ref "R23") (pin "1") (pinfunction "1_1") (pintype "passive"))
      (node (ref "R25") (pin "1") (pinfunction "1_1") (pintype "passive"))
      (node (ref "U1") (pin "1") (pinfunction "VIN_1") (pintype "power_in"))
    )
    (net (code "3") (name "+24V") (class "Default")
      (node (ref "C31") (pin "2") (pinfunction "2_2") (pintype "passive"))
      (node (ref "C32") (pin "2") (pinfunction "2_2") (pintype "passive"))
      (node (ref "C33") (pin "2") (pinfunction "2_2") (pintype "passive"))
      (node (ref "C35") (pin "2") (pinfunction "2_2") (pintype "passive"))
      (node (ref "C36") (pin "2") (pinfunction "2_2") (pintype "passive"))
      (node (ref "C37") (pin "2") (pinfunction "2_2") (pintype "passive"))
      (node (ref "C39") (pin "2") (pinfunction "2_2") (pintype "passive"))
      (node (ref "C40") (pin "2") (pinfunction "2_2") (pintype "passive"))
      (node (ref "C41") (pin "2") (pinfunction "2_2") (pintype "passive"))
      (node (ref "P8") (pin "4") (pinfunction "4_4") (pintype "passive"))
      (node (ref "P8") (pin "5") (pinfunction "5_5") (pintype "passive"))
      (node (ref "P8") (pin "6") (pinfunction "6_6") (pintype "passive"))
      (node (ref "U4") (pin "11") (pinfunction "VM_11") (pintype "passive"))
      (node (ref "U5") (pin "11") (pinfunction "VM_11") (pintype "passive"))
      (node (ref "U6") (pin "11") (pinfunction "VM_11") (pintype "passive"))
    )
    (net (code "4") (name "+A3.3V") (class "Default")
      (node (ref "C21") (pin "2") (pinfunction "2_2") (pintype "passive"))
      (node (ref "C22") (pin "2") (pinfunction "2_2") (pintype "passive"))
      (node (ref "C23") (pin "2") (pinfunction "2_2") (pintype "passive"))
      (node (ref "F1") (pin "2") (pinfunction "2_2") (pintype "passive"))
      (node (ref "U2") (pin "2") (pinfunction "VDDA_2") (pintype "power_in"))
    )
    (net (code "5") (name "/DM") (class "Default")
      (node (ref "R8") (pin "1") (pinfunction "1_1") (pintype "passive"))
      (node (ref "USB1") (pin "2") (pinfunction "D-_2") (pintype "passive"))
    )
    (net (code "6") (name "/DP") (class "Default")
      (node (ref "R9") (pin "1") (pinfunction "1_1") (pintype "passive"))
      (node (ref "USB1") (pin "3") (pinfunction "D+_3") (pintype "passive"))
    )
    (net (code "7") (name "/ENC PWM A") (class "Default")
      (node (ref "P5") (pin "3") (pinfunction "ENC_A_3") (pintype "passive"))
      (node (ref "U2") (pin "57") (pinfunction "PB5_57") (pintype "bidirectional"))
    )
    (net (code "8") (name "/ENC PWM B") (class "Default")
      (node (ref "P5") (pin "4") (pinfunction "ENC_B_4") (pintype "passive"))
      (node (ref "U2") (pin "61") (pinfunction "PD0_61") (pintype "bidirectional"))
    )
    (net (code "9") (name "/IN1_A") (class "Default")
      (node (ref "U2") (pin "13") (pinfunction "PC7_13") (pintype "bidirectional"))
      (node (ref "U4") (pin "1") (pinfunction "IN1_1") (pintype "bidirectional"))
    )
    (net (code "10") (name "/IN1_B") (class "Default")
      (node (ref "U2") (pin "15") (pinfunction "PC5_15") (pintype "bidirectional"))
      (node (ref "U5") (pin "1") (pinfunction "IN1_1") (pintype "bidirectional"))
    )
    (net (code "11") (name "/IN1_C") (class "Default")
      (node (ref "U2") (pin "47") (pinfunction "PB2/I2COSCL_47") (pintype "bidirectional"))
      (node (ref "U6") (pin "1") (pinfunction "IN1_1") (pintype "bidirectional"))
    )
    (net (code "12") (name "/IN2_A") (class "Default")
      (node (ref "U2") (pin "14") (pinfunction "PC6_14") (pintype "bidirectional"))
      (node (ref "U4") (pin "2") (pinfunction "IN2_2") (pintype "bidirectional"))
    )
    (net (code "13") (name "/IN2_B") (class "Default")
      (node (ref "U2") (pin "16") (pinfunction "PC4_16") (pintype "bidirectional"))
      (node (ref "U5") (pin "2") (pinfunction "IN2_2") (pintype "bidirectional"))
    )
    (net (code "14") (name "/IN2_C") (class "Default")
      (node (ref "U2") (pin "48") (pinfunction "PB3/I2COSDA_48") (pintype "bidirectional"))
      (node (ref "U6") (pin "2") (pinfunction "IN2_2") (pintype "bidirectional"))
    )
    (net (code "15") (name "/IPROPI_A") (class "Default")
      (node (ref "R16") (pin "1") (pinfunction "1_1") (pintype "passive"))
      (node (ref "U2") (pin "6") (pinfunction "PE3_6") (pintype "bidirectional"))
      (node (ref "U4") (pin "6") (pinfunction "IPROPI_6") (pintype "bidirectional"))
    )
    (net (code "16") (name "/IPROPI_B") (class "Default")
      (node (ref "R20") (pin "1") (pinfunction "1_1") (pintype "passive"))
      (node (ref "U2") (pin "7") (pinfunction "PE2_7") (pintype "bidirectional"))
      (node (ref "U5") (pin "6") (pinfunction "IPROPI_6") (pintype "bidirectional"))
    )
    (net (code "17") (name "/IPROPI_C") (class "Default")
      (node (ref "R24") (pin "1") (pinfunction "1_1") (pintype "passive"))
      (node (ref "U2") (pin "8") (pinfunction "PE1_8") (pintype "bidirectional"))
      (node (ref "U6") (pin "6") (pinfunction "IPROPI_6") (pintype "bidirectional"))
    )
    (net (code "18") (name "/NO1") (class "Default")
      (node (ref "P9") (pin "7") (pinfunction "7_7") (pintype "passive"))
      (node (ref "R27") (pin "1") (pinfunction "1_1") (pintype "passive"))
      (node (ref "U2") (pin "58") (pinfunction "PB4_58") (pintype "bidirectional"))
    )
    (net (code "19") (name "/NO2") (class "Default")
      (node (ref "P9") (pin "8") (pinfunction "8_8") (pintype "passive"))
      (node (ref "R28") (pin "1") (pinfunction "1_1") (pintype "passive"))
      (node (ref "U2") (pin "59") (pinfunction "PE4_59") (pintype "bidirectional"))
    )
    (net (code "20") (name "/NO3") (class "Default")
      (node (ref "P9") (pin "9") (pinfunction "9_9") (pintype "passive"))
      (node (ref "R29") (pin "1") (pinfunction "1_1") (pintype "passive"))
      (node (ref "U2") (pin "60") (pinfunction "PE5_60") (pintype "bidirectional"))
    )
    (net (code "21") (name "/NO4") (class "Default")
      (node (ref "P9") (pin "10") (pinfunction "10_10") (pintype "passive"))
      (node (ref "R30") (pin "1") (pinfunction "1_1") (pintype "passive"))
      (node (ref "U2") (pin "62") (pinfunction "PD1_62") (pintype "bidirectional"))
    )
    (net (code "22") (name "/NO5") (class "Default")
      (node (ref "P9") (pin "11") (pinfunction "11_11") (pintype "passive"))
      (node (ref "R31") (pin "1") (pinfunction "1_1") (pintype "passive"))
      (node (ref "U2") (pin "63") (pinfunction "PD2_63") (pintype "bidirectional"))
    )
    (net (code "23") (name "/NO6") (class "Default")
      (node (ref "P9") (pin "12") (pinfunction "12_12") (pintype "passive"))
      (node (ref "R32") (pin "1") (pinfunction "1_1") (pintype "passive"))
      (node (ref "U2") (pin "64") (pinfunction "PD3_64") (pintype "bidirectional"))
    )
    (net (code "24") (name "/OSC0") (class "Default")
      (node (ref "C18") (pin "2") (pinfunction "2_2") (pintype "passive"))
      (node (ref "U2") (pin "40") (pinfunction "OSC0_40") (pintype "input"))
      (node (ref "X1") (pin "1") (pintype "passive"))
    )
    (net (code "25") (name "/OSC1") (class "Default")
      (node (ref "C19") (pin "2") (pinfunction "2_2") (pintype "passive"))
      (node (ref "U2") (pin "41") (pinfunction "OSC1_41") (pintype "output"))
      (node (ref "X1") (pin "3") (pintype "passive"))
    )
    (net (code "26") (name "/OUT1_A") (class "Default")
      (node (ref "P2") (pin "2") (pinfunction "GND_2") (pintype "passive"))
      (node (ref "U4") (pin "8") (pinfunction "OUT1_8") (pintype "bidirectional"))
    )
    (net (code "27") (name "/OUT1_B") (class "Default")
      (node (ref "P3") (pin "2") (pinfunction "GND_2") (pintype "passive"))
      (node (ref "U5") (pin "8") (pinfunction "OUT1_8") (pintype "bidirectional"))
    )
    (net (code "28") (name "/OUT1_C") (class "Default")
      (node (ref "P4") (pin "2") (pinfunction "GND_2") (pintype "passive"))
      (node (ref "U6") (pin "8") (pinfunction "OUT1_8") (pintype "bidirectional"))
    )
    (net (code "29") (name "/OUT2_A") (class "Default")
      (node (ref "P2") (pin "1") (pinfunction "VCC_1") (pintype "passive"))
      (node (ref "U4") (pin "10") (pinfunction "OUT2_10") (pintype "bidirectional"))
    )
    (net (code "30") (name "/OUT2_B") (class "Default")
      (node (ref "P3") (pin "1") (pinfunction "VCC_1") (pintype "passive"))
      (node (ref "U5") (pin "10") (pinfunction "OUT2_10") (pintype "bidirectional"))
    )
    (net (code "31") (name "/OUT2_C") (class "Default")
      (node (ref "P4") (pin "1") (pinfunction "VCC_1") (pintype "passive"))
      (node (ref "U6") (pin "10") (pinfunction "OUT2_10") (pintype "bidirectional"))
    )
    (net (code "32") (name "/RESET") (class "Default")
      (node (ref "C27") (pin "2") (pinfunction "2_2") (pintype "passive"))
      (node (ref "R3") (pin "2") (pinfunction "2_2") (pintype "passive"))
      (node (ref "U2") (pin "38") (pinfunction "RESET_38") (pintype "input"))
    )
    (net (code "33") (name "/SHIELD") (class "Default")
      (node (ref "C2") (pin "2") (pinfunction "2_2") (pintype "passive"))
      (node (ref "R1") (pin "2") (pinfunction "2_2") (pintype "passive"))
      (node (ref "USB1") (pin "5") (pinfunction "SHIELD_5") (pintype "passive"))
      (node (ref "USB1") (pin "6") (pinfunction "SHIELD_6") (pintype "passive"))
    )
    (net (code "34") (name "/TCK") (class "Default")
      (node (ref "P1") (pin "2") (pinfunction "2_2") (pintype "passive"))
      (node (ref "R2") (pin "2") (pinfunction "2_2") (pintype "passive"))
      (node (ref "U2") (pin "52") (pinfunction "PC0/TCK/SWCLK_52") (pintype "bidirectional"))
    )
    (net (code "35") (name "/TDI") (class "Default")
      (node (ref "P1") (pin "4") (pinfunction "4_4") (pintype "passive"))
      (node (ref "U2") (pin "50") (pinfunction "PC2/TDI_50") (pintype "bidirectional"))
    )
    (net (code "36") (name "/TDO") (class "Default")
      (node (ref "P1") (pin "3") (pinfunction "3_3") (pintype "passive"))
      (node (ref "U2") (pin "49") (pinfunction "PC3/TDO/SWO_49") (pintype "bidirectional"))
    )
    (net (code "37") (name "/TMS") (class "Default")
      (node (ref "P1") (pin "5") (pinfunction "5_5") (pintype "passive"))
      (node (ref "U2") (pin "51") (pinfunction "PC1/TMS/SWDIO_51") (pintype "bidirectional"))
    )
    (net (code "38") (name "/USB RX LED") (class "Default")
      (node (ref "D2") (pin "2") (pinfunction "K_2") (pintype "passive"))
      (node (ref "U3") (pin "5") (pinfunction "CBUS2_5") (pintype "passive"))
    )
    (net (code "39") (name "/USB TX LED") (class "Default")
      (node (ref "D1") (pin "2") (pinfunction "K_2") (pintype "passive"))
      (node (ref "U3") (pin "11") (pinfunction "CBUS1_11") (pintype "passive"))
    )
    (net (code "40") (name "/USB_RX") (class "Default")
      (node (ref "R4") (pin "1") (pinfunction "1_1") (pintype "passive"))
      (node (ref "U2") (pin "17") (pinfunction "PA0/U0RX_17") (pintype "bidirectional"))
      (node (ref "U3") (pin "15") (pinfunction "TXD_15") (pintype "passive"))
    )
    (net (code "41") (name "/USB_TX") (class "Default")
      (node (ref "R5") (pin "1") (pinfunction "1_1") (pintype "passive"))
      (node (ref "U2") (pin "18") (pinfunction "PA1/U0TX_18") (pintype "bidirectional"))
      (node (ref "U3") (pin "2") (pinfunction "RXD_2") (pintype "passive"))
    )
    (net (code "42") (name "/VCORE") (class "Default")
      (node (ref "C24") (pin "2") (pinfunction "2_2") (pintype "passive"))
      (node (ref "C25") (pin "2") (pinfunction "2_2") (pintype "passive"))
      (node (ref "C26") (pin "2") (pinfunction "2_2") (pintype "passive"))
      (node (ref "U2") (pin "25") (pinfunction "VDDC_25") (pintype "power_in"))
      (node (ref "U2") (pin "56") (pinfunction "VDDC_56") (pintype "power_in"))
    )
    (net (code "43") (name "/VREF_A") (class "Default")
      (node (ref "R17") (pin "2") (pinfunction "2_2") (pintype "passive"))
      (node (ref "R18") (pin "1") (pinfunction "1_1") (pintype "passive"))
      (node (ref "U4") (pin "5") (pinfunction "VREF_5") (pintype "power_in"))
    )
    (net (code "44") (name "/VREF_B") (class "Default")
      (node (ref "R21") (pin "2") (pinfunction "2_2") (pintype "passive"))
      (node (ref "R22") (pin "1") (pinfunction "1_1") (pintype "passive"))
      (node (ref "U5") (pin "5") (pinfunction "VREF_5") (pintype "power_in"))
    )
    (net (code "45") (name "/VREF_C") (class "Default")
      (node (ref "R25") (pin "2") (pinfunction "2_2") (pintype "passive"))
      (node (ref "R26") (pin "1") (pinfunction "1_1") (pintype "passive"))
      (node (ref "U6") (pin "5") (pinfunction "VREF_5") (pintype "power_in"))
    )
    (net (code "46") (name "/nFLT_A") (class "Default")
      (node (ref "R15") (pin "1") (pinfunction "1_1") (pintype "passive"))
      (node (ref "U2") (pin "31") (pinfunction "PF3_31") (pintype "bidirectional"))
      (node (ref "U4") (pin "4") (pinfunction "nFAULT_4") (pintype "input"))
    )
    (net (code "47") (name "/nFLT_B") (class "Default")
      (node (ref "R19") (pin "2") (pinfunction "2_2") (pintype "passive"))
      (node (ref "U2") (pin "23") (pinfunction "PA6_23") (pintype "bidirectional"))
      (node (ref "U5") (pin "4") (pinfunction "nFAULT_4") (pintype "input"))
    )
    (net (code "48") (name "/nFLT_C") (class "Default")
      (node (ref "R23") (pin "2") (pinfunction "2_2") (pintype "passive"))
      (node (ref "U2") (pin "46") (pinfunction "PB1/USB0VBUS_46") (pintype "bidirectional"))
      (node (ref "U6") (pin "4") (pinfunction "nFAULT_4") (pintype "input"))
    )
    (net (code "49") (name "/nSLEEP_A") (class "Default")
      (node (ref "U2") (pin "20") (pinfunction "PA3/SSI0FSS_20") (pintype "bidirectional"))
      (node (ref "U4") (pin "3") (pinfunction "nSLEEP_3") (pintype "input"))
    )
    (net (code "50") (name "/nSLEEP_B") (class "Default")
      (node (ref "U2") (pin "29") (pinfunction "PF1_29") (pintype "bidirectional"))
      (node (ref "U5") (pin "3") (pinfunction "nSLEEP_3") (pintype "input"))
    )
    (net (code "51") (name "/nSLEEP_C") (class "Default")
      (node (ref "U2") (pin "45") (pinfunction "PB0/USB0ID_45") (pintype "bidirectional"))
      (node (ref "U6") (pin "3") (pinfunction "nSLEEP_3") (pintype "input"))
    )
    (net (code "52") (name "GND") (class "Default")
      (node (ref "C1") (pin "2") (pinfunction "2_2") (pintype "passive"))
      (node (ref "C10") (pin "2") (pinfunction "2_2") (pintype "passive"))
      (node (ref "C11") (pin "2") (pinfunction "2_2") (pintype "passive"))
      (node (ref "C12") (pin "2") (pinfunction "2_2") (pintype "passive"))
      (node (ref "C13") (pin "1") (pinfunction "1_1") (pintype "passive"))
      (node (ref "C14") (pin "1") (pinfunction "1_1") (pintype "passive"))
      (node (ref "C15") (pin "1") (pinfunction "1_1") (pintype "passive"))
      (node (ref "C16") (pin "1") (pinfunction "1_1") (pintype "passive"))
      (node (ref "C17") (pin "1") (pinfunction "1_1") (pintype "passive"))
      (node (ref "C18") (pin "1") (pinfunction "1_1") (pintype "passive"))
      (node (ref "C19") (pin "1") (pinfunction "1_1") (pintype "passive"))
      (node (ref "C2") (pin "1") (pinfunction "1_1") (pintype "passive"))
      (node (ref "C20") (pin "1") (pinfunction "1_1") (pintype "passive"))
      (node (ref "C21") (pin "1") (pinfunction "1_1") (pintype "passive"))
      (node (ref "C22") (pin "1") (pinfunction "1_1") (pintype "passive"))
      (node (ref "C23") (pin "1") (pinfunction "1_1") (pintype "passive"))
      (node (ref "C24") (pin "1") (pinfunction "1_1") (pintype "passive"))
      (node (ref "C25") (pin "1") (pinfunction "1_1") (pintype "passive"))
      (node (ref "C26") (pin "1") (pinfunction "1_1") (pintype "passive"))
      (node (ref "C27") (pin "1") (pinfunction "1_1") (pintype "passive"))
      (node (ref "C28") (pin "1") (pinfunction "1_1") (pintype "passive"))
      (node (ref "C29") (pin "1") (pinfunction "1_1") (pintype "passive"))
      (node (ref "C3") (pin "1") (pinfunction "1_1") (pintype "passive"))
      (node (ref "C32") (pin "1") (pinfunction "1_1") (pintype "passive"))
      (node (ref "C33") (pin "1") (pinfunction "1_1") (pintype "passive"))
      (node (ref "C36") (pin "1") (pinfunction "1_1") (pintype "passive"))
      (node (ref "C37") (pin "1") (pinfunction "1_1") (pintype "passive"))
      (node (ref "C4") (pin "1") (pinfunction "1_1") (pintype "passive"))
      (node (ref "C40") (pin "1") (pinfunction "1_1") (pintype "passive"))
      (node (ref "C41") (pin "1") (pinfunction "1_1") (pintype "passive"))
      (node (ref "C5") (pin "1") (pinfunction "1_1") (pintype "passive"))
      (node (ref "C6") (pin "1") (pinfunction "1_1") (pintype "passive"))
      (node (ref "C7") (pin "2") (pinfunction "2_2") (pintype "passive"))
      (node (ref "C8") (pin "2") (pinfunction "2_2") (pintype "passive"))
      (node (ref "C9") (pin "1") (pinfunction "1_1") (pintype "passive"))
      (node (ref "P1") (pin "1") (pinfunction "1_1") (pintype "passive"))
      (node (ref "P5") (pin "5") (pinfunction "GND_5") (pintype "passive"))
      (node (ref "P5") (pin "6") (pinfunction "GND_6") (pintype "passive"))
      (node (ref "P8") (pin "1") (pinfunction "1_1") (pintype "passive"))
      (node (ref "P8") (pin "2") (pinfunction "2_2") (pintype "passive"))
      (node (ref "P8") (pin "3") (pinfunction "3_3") (pintype "passive"))
      (node (ref "P9") (pin "1") (pinfunction "1_1") (pintype "passive"))
      (node (ref "P9") (pin "2") (pinfunction "2_2") (pintype "passive"))
      (node (ref "P9") (pin "3") (pinfunction "3_3") (pintype "passive"))
      (node (ref "P9") (pin "4") (pinfunction "4_4") (pintype "passive"))
      (node (ref "P9") (pin "5") (pinfunction "5_5") (pintype "passive"))
      (node (ref "P9") (pin "6") (pinfunction "6_6") (pintype "passive"))
      (node (ref "R1") (pin "1") (pinfunction "1_1") (pintype "passive"))
      (node (ref "R16") (pin "2") (pinfunction "2_2") (pintype "passive"))
      (node (ref "R18") (pin "2") (pinfunction "2_2") (pintype "passive"))
      (node (ref "R20") (pin "2") (pinfunction "2_2") (pintype "passive"))
      (node (ref "R22") (pin "2") (pinfunction "2_2") (pintype "passive"))
      (node (ref "R24") (pin "2") (pinfunction "2_2") (pintype "passive"))
      (node (ref "R26") (pin "2") (pinfunction "2_2") (pintype "passive"))
      (node (ref "U1") (pin "2") (pinfunction "GND_2") (pintype "power_in"))
      (node (ref "U1") (pin "4") (pinfunction "GND_4") (pintype "power_in"))
      (node (ref "U2") (pin "12") (pinfunction "GND_12") (pintype "power_in"))
      (node (ref "U2") (pin "27") (pinfunction "GND_27") (pintype "power_in"))
      (node (ref "U2") (pin "3") (pinfunction "GNDA_3") (pintype "power_in"))
      (node (ref "U2") (pin "32") (pinfunction "WAKE_32") (pintype "input"))
      (node (ref "U2") (pin "34") (pinfunction "XOSC0_34") (pintype "input"))
      (node (ref "U2") (pin "35") (pinfunction "GNDX_35") (pintype "power_in"))
      (node (ref "U2") (pin "39") (pinfunction "GND_39") (pintype "power_in"))
      (node (ref "U2") (pin "55") (pinfunction "GND_55") (pintype "power_in"))
      (node (ref "U3") (pin "13") (pinfunction "GND_13") (pintype "passive"))
      (node (ref "U3") (pin "17") (pinfunction "GND_17") (pintype "passive"))
      (node (ref "U3") (pin "3") (pinfunction "GND_3") (pintype "passive"))
      (node (ref "U4") (pin "15") (pinfunction "GND_15") (pintype "passive"))
      (node (ref "U4") (pin "16") (pinfunction "PMODE_16") (pintype "bidirectional"))
      (node (ref "U4") (pin "7") (pinfunction "IMODE_7") (pintype "bidirectional"))
      (node (ref "U4") (pin "9") (pinfunction "PGND_9") (pintype "passive"))
      (node (ref "U5") (pin "15") (pinfunction "GND_15") (pintype "passive"))
      (node (ref "U5") (pin "16") (pinfunction "PMODE_16") (pintype "bidirectional"))
      (node (ref "U5") (pin "7") (pinfunction "IMODE_7") (pintype "bidirectional"))
      (node (ref "U5") (pin "9") (pinfunction "PGND_9") (pintype "passive"))
      (node (ref "U6") (pin "15") (pinfunction "GND_15") (pintype "passive"))
      (node (ref "U6") (pin "16") (pinfunction "PMODE_16") (pintype "bidirectional"))
      (node (ref "U6") (pin "7") (pinfunction "IMODE_7") (pintype "bidirectional"))
      (node (ref "U6") (pin "9") (pinfunction "PGND_9") (pintype "passive"))
      (node (ref "USB1") (pin "4") (pinfunction "GND_4") (pintype "power_in"))
      (node (ref "X1") (pin "2") (pinfunction "CASE_2") (pintype "passive"))
      (node (ref "X1") (pin "4") (pinfunction "CASE_4") (pintype "passive"))
    )
    (net (code "53") (name "Net-(D1-A)") (class "Default")
      (node (ref "D1") (pin "1") (pinfunction "A_1") (pintype "passive"))
      (node (ref "R13") (pin "1") (pinfunction "1_1") (pintype "passive"))
    )
    (net (code "54") (name "Net-(D2-A)") (class "Default")
      (node (ref "D2") (pin "1") (pinfunction "A_1") (pintype "passive"))
      (node (ref "R14") (pin "1") (pinfunction "1_1") (pintype "passive"))
    )
    (net (code "55") (name "Net-(U3-CTS#)") (class "Default")
      (node (ref "R7") (pin "1") (pinfunction "1_1") (pintype "passive"))
      (node (ref "U3") (pin "4") (pinfunction "CTS#_4") (pintype "passive"))
    )
    (net (code "56") (name "Net-(U3-RTS#)") (class "Default")
      (node (ref "R6") (pin "1") (pinfunction "1_1") (pintype "passive"))
      (node (ref "U3") (pin "16") (pinfunction "RTS#_16") (pintype "passive"))
    )
    (net (code "57") (name "Net-(U3-USBDM)") (class "Default")
      (node (ref "R8") (pin "2") (pinfunction "2_2") (pintype "passive"))
      (node (ref "U3") (pin "7") (pinfunction "USBDM_7") (pintype "passive"))
    )
    (net (code "58") (name "Net-(U3-USBDP)") (class "Default")
      (node (ref "R9") (pin "2") (pinfunction "2_2") (pintype "passive"))
      (node (ref "U3") (pin "6") (pinfunction "USBDP_6") (pintype "passive"))
    )
    (net (code "59") (name "Net-(U4-CPH)") (class "Default")
      (node (ref "C30") (pin "2") (pinfunction "2_2") (pintype "passive"))
      (node (ref "U4") (pin "13") (pinfunction "CPH_13") (pintype "passive"))
    )
    (net (code "60") (name "Net-(U4-CPL)") (class "Default")
      (node (ref "C30") (pin "1") (pinfunction "1_1") (pintype "passive"))
      (node (ref "U4") (pin "14") (pinfunction "CPL_14") (pintype "passive"))
    )
    (net (code "61") (name "Net-(U4-VCP)") (class "Default")
      (node (ref "C31") (pin "1") (pinfunction "1_1") (pintype "passive"))
      (node (ref "U4") (pin "12") (pinfunction "VCP_12") (pintype "power_in"))
    )
    (net (code "62") (name "Net-(U5-CPH)") (class "Default")
      (node (ref "C34") (pin "2") (pinfunction "2_2") (pintype "passive"))
      (node (ref "U5") (pin "13") (pinfunction "CPH_13") (pintype "passive"))
    )
    (net (code "63") (name "Net-(U5-CPL)") (class "Default")
      (node (ref "C34") (pin "1") (pinfunction "1_1") (pintype "passive"))
      (node (ref "U5") (pin "14") (pinfunction "CPL_14") (pintype "passive"))
    )
    (net (code "64") (name "Net-(U5-VCP)") (class "Default")
      (node (ref "C35") (pin "1") (pinfunction "1_1") (pintype "passive"))
      (node (ref "U5") (pin "12") (pinfunction "VCP_12") (pintype "power_in"))
    )
    (net (code "65") (name "Net-(U6-CPH)") (class "Default")
      (node (ref "C38") (pin "2") (pinfunction "2_2") (pintype "passive"))
      (node (ref "U6") (pin "13") (pinfunction "CPH_13") (pintype "passive"))
    )
    (net (code "66") (name "Net-(U6-CPL)") (class "Default")
      (node (ref "C38") (pin "1") (pinfunction "1_1") (pintype "passive"))
      (node (ref "U6") (pin "14") (pinfunction "CPL_14") (pintype "passive"))
    )
    (net (code "67") (name "Net-(U6-VCP)") (class "Default")
      (node (ref "C39") (pin "1") (pinfunction "1_1") (pintype "passive"))
      (node (ref "U6") (pin "12") (pinfunction "VCP_12") (pintype "power_in"))
    )
    (net (code "68") (name "VBUS") (class "Default")
      (node (ref "C1") (pin "1") (pinfunction "1_1") (pintype "passive"))
      (node (ref "C3") (pin "2") (pinfunction "2_2") (pintype "passive"))
      (node (ref "L1") (pin "1") (pinfunction "1_1") (pintype "passive"))
      (node (ref "USB1") (pin "1") (pinfunction "VDD_1") (pintype "power_in"))
    )
    (net (code "69") (name "unconnected-(U2-HIB-Pad33)") (class "Default")
      (node (ref "U2") (pin "33") (pinfunction "HIB_33") (pintype "output+no_connect"))
    )
    (net (code "70") (name "unconnected-(U2-PA2{slash}SSI0CLK-Pad19)") (class "Default")
      (node (ref "U2") (pin "19") (pinfunction "PA2/SSI0CLK_19") (pintype "bidirectional"))
    )
    (net (code "71") (name "unconnected-(U2-PA4{slash}SSI0RX-Pad21)") (class "Default")
      (node (ref "U2") (pin "21") (pinfunction "PA4/SSI0RX_21") (pintype "bidirectional"))
    )
    (net (code "72") (name "unconnected-(U2-PA5{slash}SSI0TX-Pad22)") (class "Default")
      (node (ref "U2") (pin "22") (pinfunction "PA5/SSI0TX_22") (pintype "bidirectional"))
    )
    (net (code "73") (name "unconnected-(U2-PA7-Pad24)") (class "Default")
      (node (ref "U2") (pin "24") (pinfunction "PA7_24") (pintype "bidirectional"))
    )
    (net (code "74") (name "unconnected-(U2-PB6-Pad1)") (class "Default")
      (node (ref "U2") (pin "1") (pinfunction "PB6_1") (pintype "bidirectional"))
    )
    (net (code "75") (name "unconnected-(U2-PB7-Pad4)") (class "Default")
      (node (ref "U2") (pin "4") (pinfunction "PB7_4") (pintype "bidirectional"))
    )
    (net (code "76") (name "unconnected-(U2-PD4-Pad43)") (class "Default")
      (node (ref "U2") (pin "43") (pinfunction "PD4_43") (pintype "bidirectional"))
    )
    (net (code "77") (name "unconnected-(U2-PD5-Pad44)") (class "Default")
      (node (ref "U2") (pin "44") (pinfunction "PD5_44") (pintype "bidirectional"))
    )
    (net (code "78") (name "unconnected-(U2-PD6-Pad53)") (class "Default")
      (node (ref "U2") (pin "53") (pinfunction "PD6_53") (pintype "bidirectional"))
    )
    (net (code "79") (name "unconnected-(U2-PD7-Pad10)") (class "Default")
      (node (ref "U2") (pin "10") (pinfunction "PD7_10") (pintype "bidirectional"))
    )
    (net (code "80") (name "unconnected-(U2-PE0-Pad9)") (class "Default")
      (node (ref "U2") (pin "9") (pinfunction "PE0_9") (pintype "bidirectional"))
    )
    (net (code "81") (name "unconnected-(U2-PF0-Pad28)") (class "Default")
      (node (ref "U2") (pin "28") (pinfunction "PF0_28") (pintype "bidirectional"))
    )
    (net (code "82") (name "unconnected-(U2-PF2-Pad30)") (class "Default")
      (node (ref "U2") (pin "30") (pinfunction "PF2_30") (pintype "bidirectional"))
    )
    (net (code "83") (name "unconnected-(U2-PF4-Pad5)") (class "Default")
      (node (ref "U2") (pin "5") (pinfunction "PF4_5") (pintype "bidirectional"))
    )
    (net (code "84") (name "unconnected-(U2-XOSC1-Pad36)") (class "Default")
      (node (ref "U2") (pin "36") (pinfunction "XOSC1_36") (pintype "output+no_connect"))
    )
    (net (code "85") (name "unconnected-(U3-CBUS0-Pad12)") (class "Default")
      (node (ref "U3") (pin "12") (pinfunction "CBUS0_12") (pintype "passive+no_connect"))
    )
    (net (code "86") (name "unconnected-(U3-CBUS3-Pad14)") (class "Default")
      (node (ref "U3") (pin "14") (pinfunction "CBUS3_14") (pintype "passive+no_connect"))
    )
  )
)
